# awecont_shield_schematic.net
KiCad netlist of a schematic drawn in EAGLE
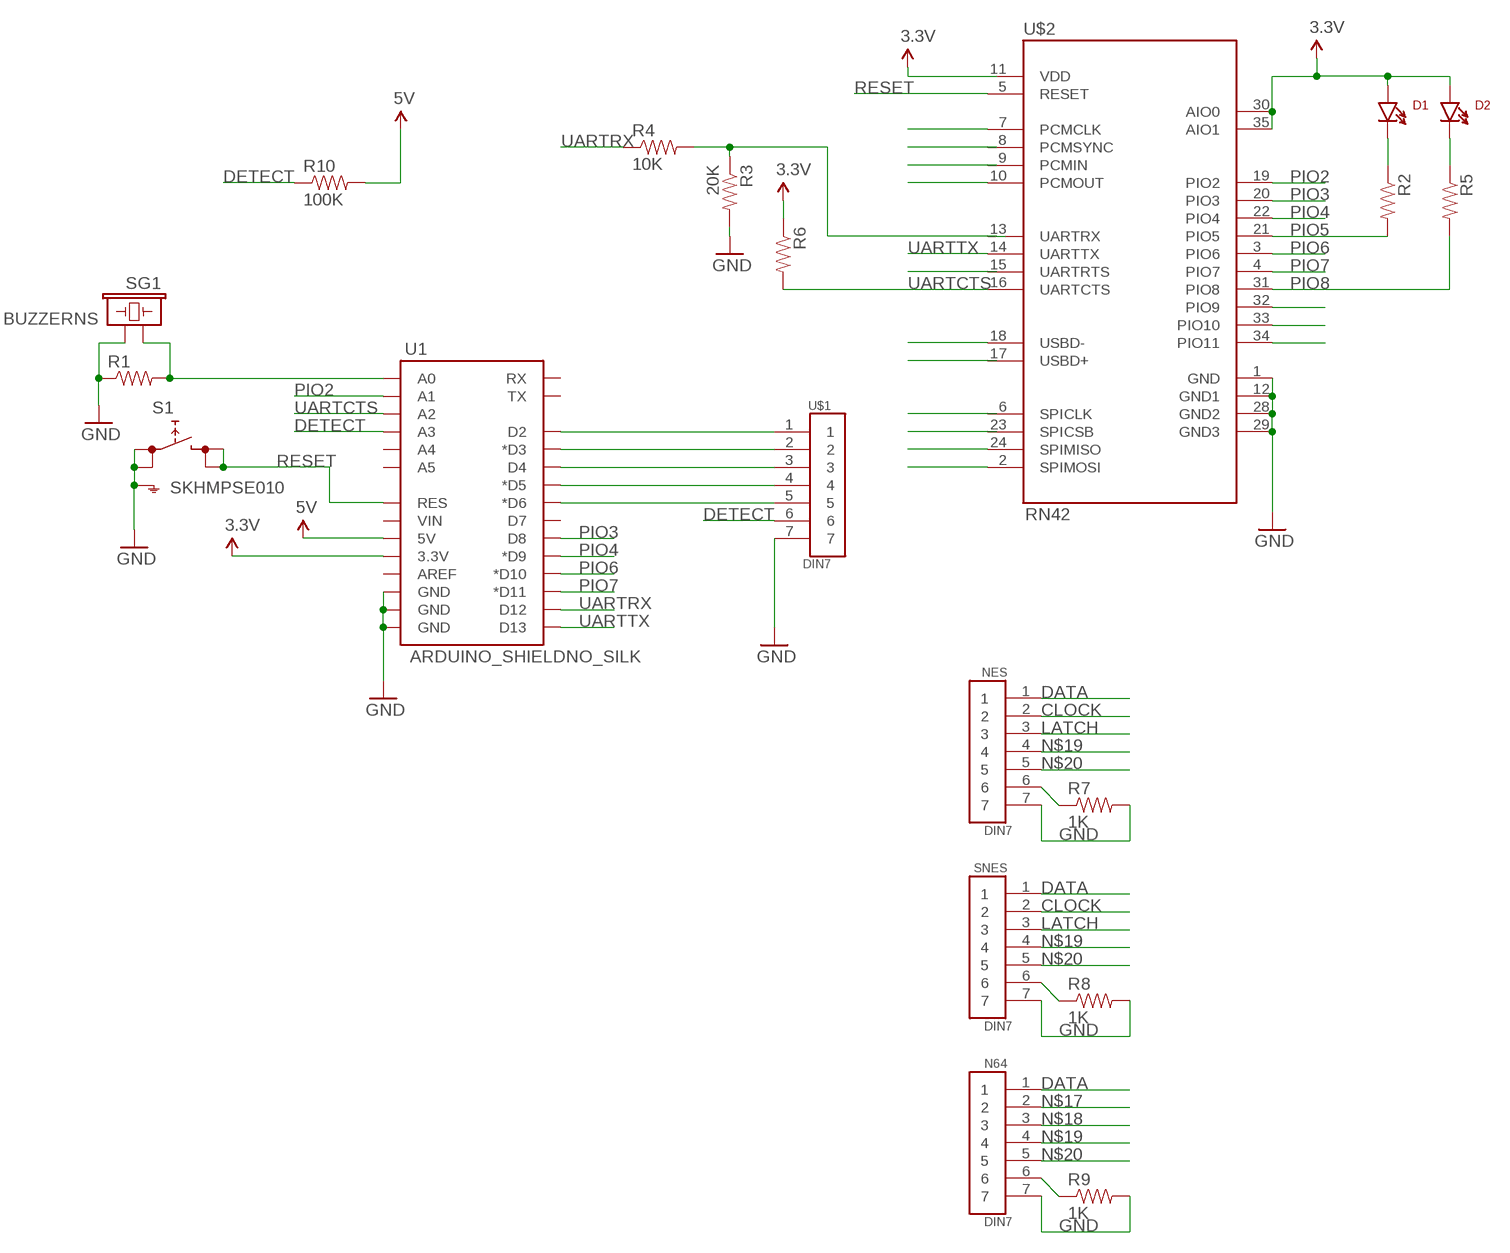
[diagram p0: schematic, sheet 1]

(export (version "E")
  (design (tool "Eeschema 10.0.6"))
  (components
    (comp (ref "D1")
      (value "LTE-302")
      (footprint "eagle-import:LTE-302")
      (libsource (lib "eagle-import") (part "LTE-302"))
    )
    (comp (ref "D2")
      (value "LTE-302")
      (footprint "eagle-import:LTE-302")
      (libsource (lib "eagle-import") (part "LTE-302"))
    )
    (comp (ref "N64")
      (value "DIN7")
      (footprint "eagle-import:DIN7")
      (libsource (lib "eagle-import") (part "DIN7"))
    )
    (comp (ref "NES")
      (value "DIN7")
      (footprint "eagle-import:DIN7")
      (libsource (lib "eagle-import") (part "DIN7"))
    )
    (comp (ref "R1")
      (value "RESISTORAXIAL-0.3")
      (footprint "eagle-import:AXIAL-0.3")
      (libsource (lib "eagle-import") (part "RESISTORAXIAL-0.3"))
    )
    (comp (ref "R2")
      (value "RESISTORAXIAL-0.3")
      (footprint "eagle-import:AXIAL-0.3")
      (libsource (lib "eagle-import") (part "RESISTORAXIAL-0.3"))
    )
    (comp (ref "R3")
      (value "20K")
      (footprint "eagle-import:AXIAL-0.3")
      (libsource (lib "eagle-import") (part "RESISTORAXIAL-0.3"))
    )
    (comp (ref "R4")
      (value "10K")
      (footprint "eagle-import:AXIAL-0.3")
      (libsource (lib "eagle-import") (part "RESISTORAXIAL-0.3"))
    )
    (comp (ref "R5")
      (value "RESISTORAXIAL-0.3")
      (footprint "eagle-import:AXIAL-0.3")
      (libsource (lib "eagle-import") (part "RESISTORAXIAL-0.3"))
    )
    (comp (ref "R6")
      (value "RESISTORAXIAL-0.3")
      (footprint "eagle-import:AXIAL-0.3")
      (libsource (lib "eagle-import") (part "RESISTORAXIAL-0.3"))
    )
    (comp (ref "R7")
      (value "1K")
      (footprint "eagle-import:AXIAL-0.3")
      (libsource (lib "eagle-import") (part "RESISTORAXIAL-0.3"))
    )
    (comp (ref "R8")
      (value "1K")
      (footprint "eagle-import:AXIAL-0.3")
      (libsource (lib "eagle-import") (part "RESISTORAXIAL-0.3"))
    )
    (comp (ref "R9")
      (value "1K")
      (footprint "eagle-import:AXIAL-0.3")
      (libsource (lib "eagle-import") (part "RESISTORAXIAL-0.3"))
    )
    (comp (ref "R10")
      (value "100K")
      (footprint "eagle-import:AXIAL-0.3")
      (libsource (lib "eagle-import") (part "RESISTORAXIAL-0.3"))
    )
    (comp (ref "S1")
      (value "SKHMPSE010")
      (footprint "eagle-import:SKHMPXE010")
      (libsource (lib "eagle-import") (part "SKHMPE010S"))
    )
    (comp (ref "SG1")
      (value "BUZZERNS")
      (footprint "eagle-import:BUZZER-12MM-NS")
      (libsource (lib "eagle-import") (part "BUZZERNS"))
    )
    (comp (ref "SNES")
      (value "DIN7")
      (footprint "eagle-import:DIN7")
      (libsource (lib "eagle-import") (part "DIN7"))
    )
    (comp (ref "U$1")
      (value "DIN7")
      (footprint "eagle-import:DIN7")
      (libsource (lib "eagle-import") (part "DIN7"))
    )
    (comp (ref "U$2")
      (value "RN42")
      (footprint "eagle-import:RN42")
      (libsource (lib "eagle-import") (part "RN42"))
    )
    (comp (ref "U1")
      (value "ARDUINO_SHIELDNO_SILK")
      (footprint "eagle-import:DUEMILANOVE_VIAS")
      (libsource (lib "eagle-import") (part "ARDUINO_SHIELDNO_SILK"))
    )
  )
  (nets
    (net (code "1") (name "/CLOCK") (class "Default")
      (node (ref "NES") (pin "2") (pinfunction "2_2") (pintype "bidirectional"))
      (node (ref "SNES") (pin "2") (pinfunction "2_2") (pintype "bidirectional"))
    )
    (net (code "2") (name "/DATA") (class "Default")
      (node (ref "N64") (pin "1") (pinfunction "1_1") (pintype "bidirectional"))
      (node (ref "NES") (pin "1") (pinfunction "1_1") (pintype "bidirectional"))
      (node (ref "SNES") (pin "1") (pinfunction "1_1") (pintype "bidirectional"))
    )
    (net (code "3") (name "/DETECT") (class "Default")
      (node (ref "R10") (pin "P$1") (pinfunction "1_P$1") (pintype "passive"))
      (node (ref "U$1") (pin "6") (pinfunction "6_6") (pintype "bidirectional"))
      (node (ref "U1") (pin "A3") (pinfunction "A3_A3") (pintype "bidirectional"))
    )
    (net (code "4") (name "/LATCH") (class "Default")
      (node (ref "NES") (pin "3") (pinfunction "3_3") (pintype "bidirectional"))
      (node (ref "SNES") (pin "3") (pinfunction "3_3") (pintype "bidirectional"))
    )
    (net (code "5") (name "/N$17") (class "Default")
      (node (ref "N64") (pin "2") (pinfunction "2_2") (pintype "bidirectional"))
    )
    (net (code "6") (name "/N$18") (class "Default")
      (node (ref "N64") (pin "3") (pinfunction "3_3") (pintype "bidirectional"))
      (node (ref "R3") (pin "P$1") (pinfunction "1_P$1") (pintype "passive"))
      (node (ref "R4") (pin "P$2") (pinfunction "2_P$2") (pintype "passive"))
    )
    (net (code "7") (name "/N$19") (class "Default")
      (node (ref "N64") (pin "4") (pinfunction "4_4") (pintype "bidirectional"))
      (node (ref "NES") (pin "4") (pinfunction "4_4") (pintype "bidirectional"))
      (node (ref "SNES") (pin "4") (pinfunction "4_4") (pintype "bidirectional"))
    )
    (net (code "8") (name "/N$20") (class "Default")
      (node (ref "N64") (pin "5") (pinfunction "5_5") (pintype "bidirectional"))
      (node (ref "NES") (pin "5") (pinfunction "5_5") (pintype "bidirectional"))
      (node (ref "SNES") (pin "5") (pinfunction "5_5") (pintype "bidirectional"))
    )
    (net (code "9") (name "/PIO2") (class "Default")
      (node (ref "U$2") (pin "19") (pinfunction "PIO2_19") (pintype "output"))
      (node (ref "U1") (pin "A1") (pinfunction "A1_A1") (pintype "bidirectional"))
    )
    (net (code "10") (name "/PIO3") (class "Default")
      (node (ref "U$2") (pin "20") (pinfunction "PIO3_20") (pintype "input"))
      (node (ref "U1") (pin "D8") (pinfunction "D8_D8") (pintype "bidirectional"))
    )
    (net (code "11") (name "/PIO4") (class "Default")
      (node (ref "U$2") (pin "22") (pinfunction "PIO4_22") (pintype "output"))
      (node (ref "U1") (pin "D9") (pinfunction "*D9_D9") (pintype "bidirectional"))
    )
    (net (code "12") (name "/PIO5") (class "Default")
      (node (ref "R2") (pin "P$2") (pinfunction "2_P$2") (pintype "passive"))
      (node (ref "U$2") (pin "21") (pinfunction "PIO5_21") (pintype "output"))
    )
    (net (code "13") (name "/PIO6") (class "Default")
      (node (ref "U$2") (pin "3") (pinfunction "PIO6_3") (pintype "input"))
      (node (ref "U1") (pin "D10") (pinfunction "*D10_D10") (pintype "bidirectional"))
    )
    (net (code "14") (name "/PIO7") (class "Default")
      (node (ref "U$2") (pin "4") (pinfunction "PIO7_4") (pintype "input"))
      (node (ref "U1") (pin "D11") (pinfunction "*D11_D11") (pintype "bidirectional"))
    )
    (net (code "15") (name "/PIO8") (class "Default")
      (node (ref "R5") (pin "P$2") (pinfunction "2_P$2") (pintype "passive"))
      (node (ref "U$2") (pin "31") (pinfunction "PIO8_31") (pintype "output"))
    )
    (net (code "16") (name "/RESET") (class "Default")
      (node (ref "S1") (pin "3") (pinfunction "2.1_3") (pintype "passive"))
      (node (ref "S1") (pin "4") (pinfunction "2.2_4") (pintype "passive"))
      (node (ref "U$2") (pin "5") (pinfunction "RESET_5") (pintype "input"))
      (node (ref "U1") (pin "RES") (pinfunction "RES_RES") (pintype "bidirectional"))
    )
    (net (code "17") (name "/UARTCTS") (class "Default")
      (node (ref "R6") (pin "P$2") (pinfunction "2_P$2") (pintype "passive"))
      (node (ref "U$2") (pin "16") (pinfunction "UARTCTS_16") (pintype "input"))
      (node (ref "U1") (pin "A2") (pinfunction "A2_A2") (pintype "bidirectional"))
    )
    (net (code "18") (name "/UARTRX") (class "Default")
      (node (ref "R4") (pin "P$1") (pinfunction "1_P$1") (pintype "passive"))
      (node (ref "U1") (pin "D12") (pinfunction "D12_D12") (pintype "bidirectional"))
    )
    (net (code "19") (name "/UARTTX") (class "Default")
      (node (ref "U$2") (pin "14") (pinfunction "UARTTX_14") (pintype "output"))
      (node (ref "U1") (pin "D13") (pinfunction "D13_D13") (pintype "bidirectional"))
    )
    (net (code "20") (name "3.3V") (class "Default")
      (node (ref "D1") (pin "A") (pinfunction "A_A") (pintype "bidirectional"))
      (node (ref "D2") (pin "A") (pinfunction "A_A") (pintype "bidirectional"))
      (node (ref "R6") (pin "P$1") (pinfunction "1_P$1") (pintype "passive"))
      (node (ref "U$2") (pin "30") (pinfunction "AIO0_30") (pintype "bidirectional"))
      (node (ref "U$2") (pin "35") (pinfunction "AIO1_35") (pintype "bidirectional"))
      (node (ref "U1") (pin "3.3V") (pinfunction "3.3V_3.3V") (pintype "bidirectional"))
    )
    (net (code "21") (name "5V") (class "Default")
      (node (ref "R10") (pin "P$2") (pinfunction "2_P$2") (pintype "passive"))
      (node (ref "U1") (pin "5V") (pinfunction "5V_5V") (pintype "bidirectional"))
    )
    (net (code "22") (name "GND") (class "Default")
      (node (ref "N64") (pin "7") (pinfunction "7_7") (pintype "bidirectional"))
      (node (ref "NES") (pin "7") (pinfunction "7_7") (pintype "bidirectional"))
      (node (ref "R1") (pin "P$1") (pinfunction "1_P$1") (pintype "passive"))
      (node (ref "R3") (pin "P$2") (pinfunction "2_P$2") (pintype "passive"))
      (node (ref "R7") (pin "P$2") (pinfunction "2_P$2") (pintype "passive"))
      (node (ref "R8") (pin "P$2") (pinfunction "2_P$2") (pintype "passive"))
      (node (ref "R9") (pin "P$2") (pinfunction "2_P$2") (pintype "passive"))
      (node (ref "S1") (pin "1") (pinfunction "1.1_1") (pintype "passive"))
      (node (ref "S1") (pin "2") (pinfunction "1.2_2") (pintype "passive"))
      (node (ref "S1") (pin "5") (pinfunction "SH_5") (pintype "passive"))
      (node (ref "SG1") (pin "-") (pinfunction "2_-") (pintype "passive"))
      (node (ref "SNES") (pin "7") (pinfunction "7_7") (pintype "bidirectional"))
      (node (ref "U$1") (pin "7") (pinfunction "7_7") (pintype "bidirectional"))
      (node (ref "U$2") (pin "1") (pinfunction "GND_1") (pintype "bidirectional"))
      (node (ref "U$2") (pin "12") (pinfunction "GND1_12") (pintype "bidirectional"))
      (node (ref "U$2") (pin "28") (pinfunction "GND2_28") (pintype "bidirectional"))
      (node (ref "U$2") (pin "29") (pinfunction "GND3_29") (pintype "bidirectional"))
      (node (ref "U1") (pin "GND@0") (pinfunction "GND_GND@0") (pintype "bidirectional"))
      (node (ref "U1") (pin "GND@1") (pinfunction "GND_GND@1") (pintype "bidirectional"))
      (node (ref "U1") (pin "GND@2") (pinfunction "GND_GND@2") (pintype "bidirectional"))
    )
    (net (code "23") (name "Net-(R1-2)") (class "Default")
      (node (ref "R1") (pin "P$2") (pinfunction "2_P$2") (pintype "passive"))
      (node (ref "SG1") (pin "+") (pinfunction "1_+") (pintype "passive"))
      (node (ref "U1") (pin "A0") (pinfunction "A0_A0") (pintype "bidirectional"))
    )
    (net (code "24") (name "Net-(R2-1)") (class "Default")
      (node (ref "D1") (pin "C") (pinfunction "C_C") (pintype "bidirectional"))
      (node (ref "R2") (pin "P$1") (pinfunction "1_P$1") (pintype "passive"))
    )
    (net (code "25") (name "Net-(R5-1)") (class "Default")
      (node (ref "D2") (pin "C") (pinfunction "C_C") (pintype "bidirectional"))
      (node (ref "R5") (pin "P$1") (pinfunction "1_P$1") (pintype "passive"))
    )
    (net (code "26") (name "Net-(R7-1)") (class "Default")
      (node (ref "NES") (pin "6") (pinfunction "6_6") (pintype "bidirectional"))
      (node (ref "R7") (pin "P$1") (pinfunction "1_P$1") (pintype "passive"))
    )
    (net (code "27") (name "Net-(R8-1)") (class "Default")
      (node (ref "R8") (pin "P$1") (pinfunction "1_P$1") (pintype "passive"))
      (node (ref "SNES") (pin "6") (pinfunction "6_6") (pintype "bidirectional"))
    )
    (net (code "28") (name "Net-(R9-1)") (class "Default")
      (node (ref "N64") (pin "6") (pinfunction "6_6") (pintype "bidirectional"))
      (node (ref "R9") (pin "P$1") (pinfunction "1_P$1") (pintype "passive"))
    )
    (net (code "29") (name "Net-(U$1-Pad1)") (class "Default")
      (node (ref "U$1") (pin "1") (pinfunction "1_1") (pintype "bidirectional"))
      (node (ref "U1") (pin "D2") (pinfunction "D2_D2") (pintype "bidirectional"))
    )
    (net (code "30") (name "Net-(U$1-Pad3)") (class "Default")
      (node (ref "U$1") (pin "3") (pinfunction "3_3") (pintype "bidirectional"))
      (node (ref "U1") (pin "D4") (pinfunction "D4_D4") (pintype "bidirectional"))
    )
    (net (code "31") (name "Net-(U1-*D3)") (class "Default")
      (node (ref "U$1") (pin "2") (pinfunction "2_2") (pintype "bidirectional"))
      (node (ref "U1") (pin "D3") (pinfunction "*D3_D3") (pintype "bidirectional"))
    )
    (net (code "32") (name "Net-(U1-*D5)") (class "Default")
      (node (ref "U$1") (pin "4") (pinfunction "4_4") (pintype "bidirectional"))
      (node (ref "U1") (pin "D5") (pinfunction "*D5_D5") (pintype "bidirectional"))
    )
    (net (code "33") (name "Net-(U1-*D6)") (class "Default")
      (node (ref "U$1") (pin "5") (pinfunction "5_5") (pintype "bidirectional"))
      (node (ref "U1") (pin "D6") (pinfunction "*D6_D6") (pintype "bidirectional"))
    )
    (net (code "34") (name "unconnected-(U$2-PCMCLK-Pad7)") (class "Default")
      (node (ref "U$2") (pin "7") (pinfunction "PCMCLK_7") (pintype "bidirectional"))
    )
    (net (code "35") (name "unconnected-(U$2-PCMIN-Pad9)") (class "Default")
      (node (ref "U$2") (pin "9") (pinfunction "PCMIN_9") (pintype "bidirectional"))
    )
    (net (code "36") (name "unconnected-(U$2-PCMOUT-Pad10)") (class "Default")
      (node (ref "U$2") (pin "10") (pinfunction "PCMOUT_10") (pintype "bidirectional"))
    )
    (net (code "37") (name "unconnected-(U$2-PCMSYNC-Pad8)") (class "Default")
      (node (ref "U$2") (pin "8") (pinfunction "PCMSYNC_8") (pintype "bidirectional"))
    )
    (net (code "38") (name "unconnected-(U$2-PIO9-Pad32)") (class "Default")
      (node (ref "U$2") (pin "32") (pinfunction "PIO9_32") (pintype "bidirectional"))
    )
    (net (code "39") (name "unconnected-(U$2-PIO10-Pad33)") (class "Default")
      (node (ref "U$2") (pin "33") (pinfunction "PIO10_33") (pintype "bidirectional"))
    )
    (net (code "40") (name "unconnected-(U$2-PIO11-Pad34)") (class "Default")
      (node (ref "U$2") (pin "34") (pinfunction "PIO11_34") (pintype "bidirectional"))
    )
    (net (code "41") (name "unconnected-(U$2-SPICLK-Pad6)") (class "Default")
      (node (ref "U$2") (pin "6") (pinfunction "SPICLK_6") (pintype "bidirectional"))
    )
    (net (code "42") (name "unconnected-(U$2-SPICSB-Pad23)") (class "Default")
      (node (ref "U$2") (pin "23") (pinfunction "SPICSB_23") (pintype "bidirectional"))
    )
    (net (code "43") (name "unconnected-(U$2-SPIMISO-Pad24)") (class "Default")
      (node (ref "U$2") (pin "24") (pinfunction "SPIMISO_24") (pintype "bidirectional"))
    )
    (net (code "44") (name "unconnected-(U$2-SPIMOSI-Pad2)") (class "Default")
      (node (ref "U$2") (pin "2") (pinfunction "SPIMOSI_2") (pintype "bidirectional"))
    )
    (net (code "45") (name "unconnected-(U$2-UARTRTS-Pad15)") (class "Default")
      (node (ref "U$2") (pin "15") (pinfunction "UARTRTS_15") (pintype "output"))
    )
    (net (code "46") (name "unconnected-(U$2-UARTRX-Pad13)") (class "Default")
      (node (ref "U$2") (pin "13") (pinfunction "UARTRX_13") (pintype "input"))
    )
    (net (code "47") (name "unconnected-(U$2-USBD+-Pad17)") (class "Default")
      (node (ref "U$2") (pin "17") (pinfunction "USBD+_17") (pintype "bidirectional"))
    )
    (net (code "48") (name "unconnected-(U$2-USBD--Pad18)") (class "Default")
      (node (ref "U$2") (pin "18") (pinfunction "USBD-_18") (pintype "bidirectional"))
    )
    (net (code "49") (name "unconnected-(U$2-VDD-Pad11)") (class "Default")
      (node (ref "U$2") (pin "11") (pinfunction "VDD_11") (pintype "bidirectional"))
    )
    (net (code "50") (name "unconnected-(U1-PadA4)") (class "Default")
      (node (ref "U1") (pin "A4") (pinfunction "A4_A4") (pintype "bidirectional"))
    )
    (net (code "51") (name "unconnected-(U1-PadA5)") (class "Default")
      (node (ref "U1") (pin "A5") (pinfunction "A5_A5") (pintype "bidirectional"))
    )
    (net (code "52") (name "unconnected-(U1-PadAREF)") (class "Default")
      (node (ref "U1") (pin "AREF") (pinfunction "AREF_AREF") (pintype "bidirectional"))
    )
    (net (code "53") (name "unconnected-(U1-PadD7)") (class "Default")
      (node (ref "U1") (pin "D7") (pinfunction "D7_D7") (pintype "bidirectional"))
    )
    (net (code "54") (name "unconnected-(U1-PadRX)") (class "Default")
      (node (ref "U1") (pin "RX") (pinfunction "RX_RX") (pintype "bidirectional"))
    )
    (net (code "55") (name "unconnected-(U1-PadTX)") (class "Default")
      (node (ref "U1") (pin "TX") (pinfunction "TX_TX") (pintype "bidirectional"))
    )
    (net (code "56") (name "unconnected-(U1-PadVIN)") (class "Default")
      (node (ref "U1") (pin "VIN") (pinfunction "VIN_VIN") (pintype "bidirectional"))
    )
  )
)
